# 12V51A_MC34063.net
KiCad netlist of a schematic drawn in EAGLE
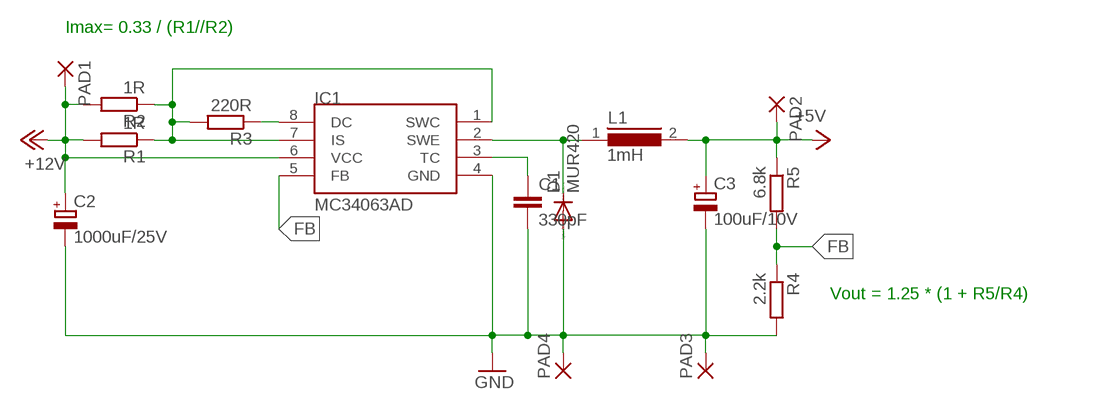
[diagram p0: schematic, sheet 1]

(export (version "E")
  (design (tool "Eeschema 10.0.6"))
  (components
    (comp (ref "C1")
      (value "330pF")
      (footprint "eagle-import:C050-024X044")
      (libsource (lib "eagle-import") (part "C-EU050-024X044"))
    )
    (comp (ref "C2")
      (value "1000uF/25V")
      (footprint "eagle-import:E2,5-7")
      (libsource (lib "eagle-import") (part "CPOL-EUE2.5-7"))
    )
    (comp (ref "C3")
      (value "100uF/10V")
      (footprint "eagle-import:E2,5-7")
      (libsource (lib "eagle-import") (part "CPOL-EUE2.5-7"))
    )
    (comp (ref "D1")
      (value "MUR420")
      (footprint "eagle-import:DO35-7")
      (libsource (lib "eagle-import") (part "1N4148DO35-7"))
    )
    (comp (ref "IC1")
      (value "MC34063AD")
      (footprint "eagle-import:SOIC8")
      (libsource (lib "eagle-import") (part "MC34063AD"))
    )
    (comp (ref "L1")
      (value "1mH")
      (footprint "eagle-import:82114R")
      (libsource (lib "eagle-import") (part "82114R"))
    )
    (comp (ref "PAD1")
      (value "2,54/1,0")
      (footprint "eagle-import:2,54_1,0")
      (libsource (lib "eagle-import") (part "2,54/1,0"))
    )
    (comp (ref "PAD2")
      (value "2,54/1,0")
      (footprint "eagle-import:2,54_1,0")
      (libsource (lib "eagle-import") (part "2,54/1,0"))
    )
    (comp (ref "PAD3")
      (value "2,54/1,0")
      (footprint "eagle-import:2,54_1,0")
      (libsource (lib "eagle-import") (part "2,54/1,0"))
    )
    (comp (ref "PAD4")
      (value "2,54/1,0")
      (footprint "eagle-import:2,54_1,0")
      (libsource (lib "eagle-import") (part "2,54/1,0"))
    )
    (comp (ref "R1")
      (value "1R")
      (footprint "eagle-import:0204_7")
      (libsource (lib "eagle-import") (part "R-EU_0204/7"))
    )
    (comp (ref "R2")
      (value "1R")
      (footprint "eagle-import:0204_7")
      (libsource (lib "eagle-import") (part "R-EU_0204/7"))
    )
    (comp (ref "R3")
      (value "220R")
      (footprint "eagle-import:0204_7")
      (libsource (lib "eagle-import") (part "R-EU_0204/7"))
    )
    (comp (ref "R4")
      (value "2.2k")
      (footprint "eagle-import:0204_7")
      (libsource (lib "eagle-import") (part "R-EU_0204/7"))
    )
    (comp (ref "R5")
      (value "6.8k")
      (footprint "eagle-import:0204_7")
      (libsource (lib "eagle-import") (part "R-EU_0204/7"))
    )
  )
  (nets
    (net (code "1") (name "+5V") (class "Default")
      (node (ref "C3") (pin "+") (pinfunction "+_+") (pintype "passive"))
      (node (ref "L1") (pin "2") (pinfunction "2_2") (pintype "passive"))
      (node (ref "PAD2") (pin "1") (pinfunction "P_1") (pintype "passive"))
      (node (ref "R5") (pin "1") (pinfunction "1_1") (pintype "passive"))
    )
    (net (code "2") (name "+12V") (class "Default")
      (node (ref "C2") (pin "+") (pinfunction "+_+") (pintype "passive"))
      (node (ref "IC1") (pin "6") (pinfunction "VCC_6") (pintype "passive"))
      (node (ref "PAD1") (pin "1") (pinfunction "P_1") (pintype "passive"))
      (node (ref "R1") (pin "2") (pinfunction "2_2") (pintype "passive"))
      (node (ref "R2") (pin "2") (pinfunction "2_2") (pintype "passive"))
    )
    (net (code "3") (name "FB") (class "Default")
      (node (ref "IC1") (pin "5") (pinfunction "FB_5") (pintype "passive"))
      (node (ref "R4") (pin "1") (pinfunction "1_1") (pintype "passive"))
      (node (ref "R5") (pin "2") (pinfunction "2_2") (pintype "passive"))
    )
    (net (code "4") (name "GND") (class "Default")
      (node (ref "C1") (pin "2") (pinfunction "2_2") (pintype "passive"))
      (node (ref "C2") (pin "-") (pinfunction "-_-") (pintype "passive"))
      (node (ref "C3") (pin "-") (pinfunction "-_-") (pintype "passive"))
      (node (ref "D1") (pin "A") (pinfunction "A_A") (pintype "passive"))
      (node (ref "IC1") (pin "4") (pinfunction "GND_4") (pintype "passive"))
      (node (ref "PAD3") (pin "1") (pinfunction "P_1") (pintype "passive"))
      (node (ref "PAD4") (pin "1") (pinfunction "P_1") (pintype "passive"))
      (node (ref "R4") (pin "2") (pinfunction "2_2") (pintype "passive"))
    )
    (net (code "5") (name "Net-(IC1-DC)") (class "Default")
      (node (ref "IC1") (pin "8") (pinfunction "DC_8") (pintype "passive"))
      (node (ref "R3") (pin "1") (pinfunction "1_1") (pintype "passive"))
    )
    (net (code "6") (name "Net-(IC1-IS)") (class "Default")
      (node (ref "IC1") (pin "1") (pinfunction "SWC_1") (pintype "passive"))
      (node (ref "IC1") (pin "7") (pinfunction "IS_7") (pintype "passive"))
      (node (ref "R1") (pin "1") (pinfunction "1_1") (pintype "passive"))
      (node (ref "R2") (pin "1") (pinfunction "1_1") (pintype "passive"))
      (node (ref "R3") (pin "2") (pinfunction "2_2") (pintype "passive"))
    )
    (net (code "7") (name "Net-(IC1-SWE)") (class "Default")
      (node (ref "D1") (pin "C") (pinfunction "C_C") (pintype "passive"))
      (node (ref "IC1") (pin "2") (pinfunction "SWE_2") (pintype "passive"))
      (node (ref "L1") (pin "1") (pinfunction "1_1") (pintype "passive"))
    )
    (net (code "8") (name "Net-(IC1-TC)") (class "Default")
      (node (ref "C1") (pin "1") (pinfunction "1_1") (pintype "passive"))
      (node (ref "IC1") (pin "3") (pinfunction "TC_3") (pintype "passive"))
    )
  )
)
